# SCH_ESQUEMA_EASY_EDA_2026-10-01.net
KiCad netlist of a schematic drawn in EasyEDA
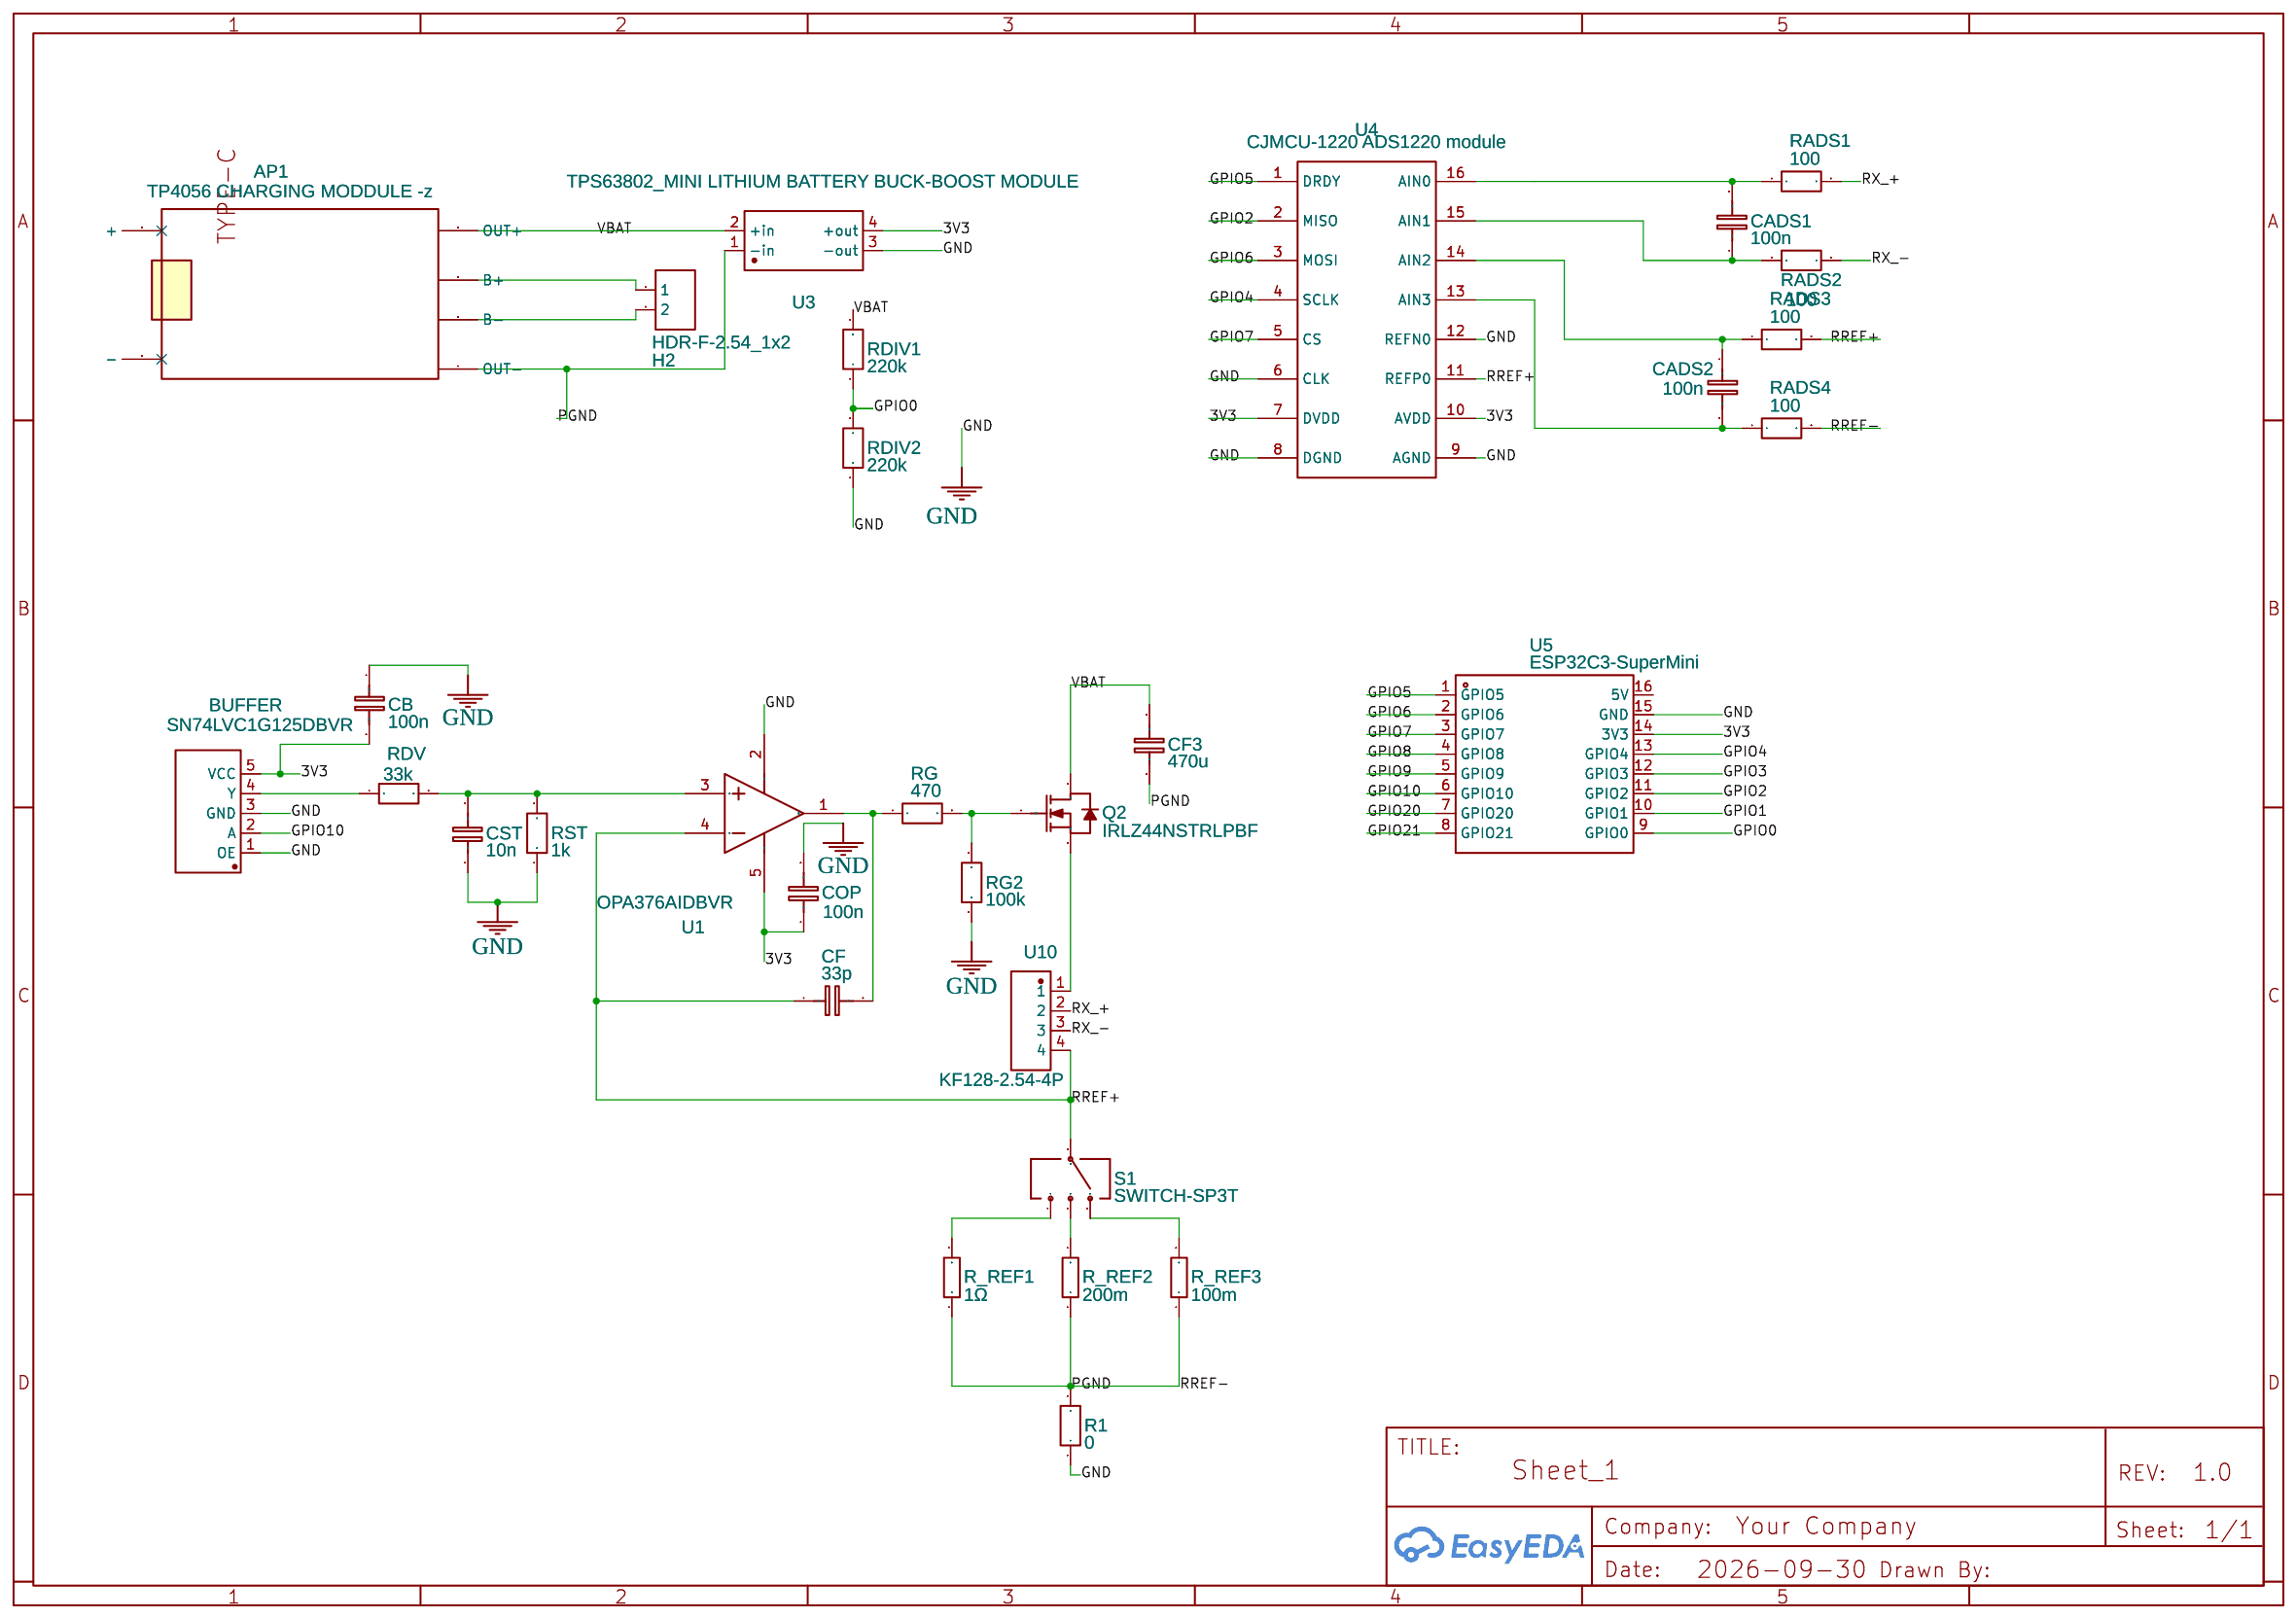
[diagram p0: schematic sheet]

(export (version "E")
  (design (tool "Eeschema 10.0.6"))
  (components
    (comp (ref "AP1")
      (value "TP4056 CHARGING MODDULE -z")
      (fields (field (name "Manufacturer Part") "TP4056"))
      (libsource (lib "") (part "TP4056 CHARGING MODDULE"))
    )
    (comp (ref "BUFFER")
      (value "SN74LVC1G125DBVR")
      (fields (field (name "Manufacturer") "TI(德州仪器)"))
      (libsource (lib "") (part "SN74LVC1G125DBVR"))
    )
    (comp (ref "CADS1") (value "100n") (libsource (lib "") (part "C_0603_EU_3")))
    (comp (ref "CADS2") (value "100n") (libsource (lib "") (part "C_0603_EU_6")))
    (comp (ref "CB") (value "100n") (libsource (lib "") (part "C_0603_EU_2")))
    (comp (ref "CF") (value "33p") (libsource (lib "") (part "C_0603_EU")))
    (comp (ref "CF3") (value "470u") (libsource (lib "") (part "C_0603_EU_1")))
    (comp (ref "COP") (value "100n") (libsource (lib "") (part "C_0603_EU_5")))
    (comp (ref "CST") (value "10n") (libsource (lib "") (part "C_0603_EU_4")))
    (comp (ref "H2") (value "HDR-F-2.54_1x2") (libsource (lib "") (part "HDR-F-2.54_1x2")))
    (comp (ref "Q2")
      (value "IRLZ44NSTRLPBF")
      (fields (field (name "Manufacturer") "Infineon(英飞凌)"))
      (libsource (lib "") (part "IRLZ44NSTRLPBF"))
    )
    (comp (ref "R1") (value "0") (libsource (lib "") (part "R_0603_EU_4")))
    (comp (ref "RADS1") (value "100") (libsource (lib "") (part "R_0603_EU_2")))
    (comp (ref "RADS2") (value "100") (libsource (lib "") (part "R_0603_EU_2")))
    (comp (ref "RADS3") (value "100") (libsource (lib "") (part "R_0603_EU_2")))
    (comp (ref "RADS4") (value "100") (libsource (lib "") (part "R_0603_EU_2")))
    (comp (ref "RDIV1") (value "220k") (libsource (lib "") (part "R_0603_EU_1")))
    (comp (ref "RDIV2") (value "220k") (libsource (lib "") (part "R_0603_EU_1")))
    (comp (ref "RDV") (value "33k") (libsource (lib "") (part "R_0603_EU")))
    (comp (ref "RG") (value "470") (libsource (lib "") (part "R_0603_EU_3")))
    (comp (ref "RG2") (value "100k") (libsource (lib "") (part "R_0603_EU_6")))
    (comp (ref "RST") (value "1k") (libsource (lib "") (part "R_0603_EU_5")))
    (comp (ref "R_REF1")
      (value "1Ω")
      (fields (field (name "Manufacturer Part") "RC1206FR-071RL") (field (name "Manufacturer") "YAGEO(国巨)"))
      (libsource (lib "") (part "RC1206FR-071RL"))
    )
    (comp (ref "R_REF2")
      (value "200m")
      (fields (field (name "Manufacturer Part") "0.16Ω±1%2W-2512"))
      (libsource (lib "") (part "0.16Ω±1%2W-2512"))
    )
    (comp (ref "R_REF3")
      (value "100m")
      (fields (field (name "Manufacturer Part") "0.16Ω±1%2W-2512"))
      (libsource (lib "") (part "0.16Ω±1%2W-2512"))
    )
    (comp (ref "S1") (value "SWITCH-SP3T") (libsource (lib "") (part "SWITCH-SP3T")))
    (comp (ref "U1")
      (value "OPA376AIDBVR")
      (fields (field (name "Manufacturer") "TI(德州仪器)"))
      (libsource (lib "") (part "OPA376AIDBVR"))
    )
    (comp (ref "U3")
      (value "TPS63802_MINI LITHIUM BATTERY BUCK-BOOST MODULE")
      (libsource (lib "") (part "TPS63802_MINI LITHIUM BATTERY BUCK-BOOST MODULE"))
    )
    (comp (ref "U4")
      (value "CJMCU-1220 ADS1220 module")
      (libsource (lib "") (part "CJMCU-1220 ADS1220 module"))
    )
    (comp (ref "U5") (value "ESP32C3-SuperMini") (libsource (lib "") (part "ESP32C3-SuperMini")))
    (comp (ref "U10")
      (value "KF128-2.54-4P")
      (fields (field (name "Manufacturer") "KEFA(科发)"))
      (libsource (lib "") (part "KF128-2.54-4P"))
    )
  )
  (nets
    (net (code "1") (name "/3V3") (class "Default")
      (node (ref "BUFFER") (pin "5") (pinfunction "VCC_5") (pintype "unspecified"))
      (node (ref "CB") (pin "2") (pinfunction "2_2") (pintype "unspecified"))
      (node (ref "COP") (pin "1") (pinfunction "1_1") (pintype "unspecified"))
      (node (ref "U1") (pin "5") (pinfunction "V+_5") (pintype "passive"))
      (node (ref "U3") (pin "4") (pinfunction "+out_4") (pintype "unspecified"))
      (node (ref "U4") (pin "10") (pinfunction "AVDD_10") (pintype "unspecified"))
      (node (ref "U4") (pin "7") (pinfunction "DVDD_7") (pintype "unspecified"))
      (node (ref "U5") (pin "14") (pinfunction "3V3_14") (pintype "unspecified"))
    )
    (net (code "2") (name "/GPIO0") (class "Default")
      (node (ref "RDIV1") (pin "1") (pinfunction "1_1") (pintype "unspecified"))
      (node (ref "RDIV2") (pin "2") (pinfunction "2_2") (pintype "unspecified"))
      (node (ref "U5") (pin "9") (pinfunction "GPIO0_9") (pintype "unspecified"))
    )
    (net (code "3") (name "/GPIO1") (class "Default")
      (node (ref "U5") (pin "10") (pinfunction "GPIO1_10") (pintype "unspecified"))
    )
    (net (code "4") (name "/GPIO2") (class "Default")
      (node (ref "U4") (pin "2") (pinfunction "MISO_2") (pintype "unspecified"))
      (node (ref "U5") (pin "11") (pinfunction "GPIO2_11") (pintype "unspecified"))
    )
    (net (code "5") (name "/GPIO3") (class "Default")
      (node (ref "U5") (pin "12") (pinfunction "GPIO3_12") (pintype "unspecified"))
    )
    (net (code "6") (name "/GPIO4") (class "Default")
      (node (ref "U4") (pin "4") (pinfunction "SCLK_4") (pintype "unspecified"))
      (node (ref "U5") (pin "13") (pinfunction "GPIO4_13") (pintype "unspecified"))
    )
    (net (code "7") (name "/GPIO5") (class "Default")
      (node (ref "U4") (pin "1") (pinfunction "DRDY_1") (pintype "unspecified"))
      (node (ref "U5") (pin "1") (pinfunction "GPIO5_1") (pintype "unspecified"))
    )
    (net (code "8") (name "/GPIO6") (class "Default")
      (node (ref "U4") (pin "3") (pinfunction "MOSI_3") (pintype "unspecified"))
      (node (ref "U5") (pin "2") (pinfunction "GPIO6_2") (pintype "unspecified"))
    )
    (net (code "9") (name "/GPIO7") (class "Default")
      (node (ref "U4") (pin "5") (pinfunction "CS_5") (pintype "unspecified"))
      (node (ref "U5") (pin "3") (pinfunction "GPIO7_3") (pintype "unspecified"))
    )
    (net (code "10") (name "/GPIO8") (class "Default")
      (node (ref "U5") (pin "4") (pinfunction "GPIO8_4") (pintype "unspecified"))
    )
    (net (code "11") (name "/GPIO9") (class "Default")
      (node (ref "U5") (pin "5") (pinfunction "GPIO9_5") (pintype "unspecified"))
    )
    (net (code "12") (name "/GPIO10") (class "Default")
      (node (ref "BUFFER") (pin "2") (pinfunction "A_2") (pintype "unspecified"))
      (node (ref "U5") (pin "6") (pinfunction "GPIO10_6") (pintype "unspecified"))
    )
    (net (code "13") (name "/GPIO20") (class "Default")
      (node (ref "U5") (pin "7") (pinfunction "GPIO20_7") (pintype "unspecified"))
    )
    (net (code "14") (name "/GPIO21") (class "Default")
      (node (ref "U5") (pin "8") (pinfunction "GPIO21_8") (pintype "unspecified"))
    )
    (net (code "15") (name "/PGND") (class "Default")
      (node (ref "AP1") (pin "4") (pinfunction "OUT-_4") (pintype "unspecified"))
      (node (ref "CF3") (pin "1") (pinfunction "1_1") (pintype "unspecified"))
      (node (ref "R1") (pin "2") (pinfunction "2_2") (pintype "unspecified"))
      (node (ref "RADS4") (pin "2") (pinfunction "2_2") (pintype "unspecified"))
      (node (ref "R_REF1") (pin "1") (pinfunction "1_1") (pintype "input"))
      (node (ref "R_REF2") (pin "1") (pinfunction "1_1") (pintype "unspecified"))
      (node (ref "R_REF3") (pin "1") (pinfunction "1_1") (pintype "unspecified"))
      (node (ref "U3") (pin "1") (pinfunction "-in_1") (pintype "unspecified"))
    )
    (net (code "16") (name "/RREF+") (class "Default")
      (node (ref "CF") (pin "1") (pinfunction "1_1") (pintype "unspecified"))
      (node (ref "RADS3") (pin "2") (pinfunction "2_2") (pintype "unspecified"))
      (node (ref "S1") (pin "3") (pinfunction "3_3") (pintype "unspecified"))
      (node (ref "U1") (pin "4") (pinfunction "IN-_4") (pintype "unspecified"))
      (node (ref "U10") (pin "4") (pinfunction "4_4") (pintype "unspecified"))
      (node (ref "U4") (pin "11") (pinfunction "REFP0_11") (pintype "unspecified"))
    )
    (net (code "17") (name "/RX_+") (class "Default")
      (node (ref "RADS1") (pin "2") (pinfunction "2_2") (pintype "unspecified"))
      (node (ref "U10") (pin "2") (pinfunction "2_2") (pintype "unspecified"))
    )
    (net (code "18") (name "/RX_-") (class "Default")
      (node (ref "RADS2") (pin "2") (pinfunction "2_2") (pintype "unspecified"))
      (node (ref "U10") (pin "3") (pinfunction "3_3") (pintype "unspecified"))
    )
    (net (code "19") (name "/VBAT") (class "Default")
      (node (ref "AP1") (pin "3") (pinfunction "OUT+_3") (pintype "unspecified"))
      (node (ref "CF3") (pin "2") (pinfunction "2_2") (pintype "unspecified"))
      (node (ref "Q2") (pin "2") (pinfunction "D_2") (pintype "unspecified"))
      (node (ref "RDIV1") (pin "2") (pinfunction "2_2") (pintype "unspecified"))
      (node (ref "U3") (pin "2") (pinfunction "+in_2") (pintype "unspecified"))
    )
    (net (code "20") (name "GND") (class "Default")
      (node (ref "BUFFER") (pin "1") (pinfunction "OE_1") (pintype "unspecified"))
      (node (ref "BUFFER") (pin "3") (pinfunction "GND_3") (pintype "unspecified"))
      (node (ref "CB") (pin "1") (pinfunction "1_1") (pintype "unspecified"))
      (node (ref "COP") (pin "2") (pinfunction "2_2") (pintype "unspecified"))
      (node (ref "CST") (pin "1") (pinfunction "1_1") (pintype "unspecified"))
      (node (ref "R1") (pin "1") (pinfunction "1_1") (pintype "unspecified"))
      (node (ref "RDIV2") (pin "1") (pinfunction "1_1") (pintype "unspecified"))
      (node (ref "RG2") (pin "1") (pinfunction "1_1") (pintype "unspecified"))
      (node (ref "RST") (pin "1") (pinfunction "1_1") (pintype "unspecified"))
      (node (ref "U1") (pin "2") (pinfunction "V-_2") (pintype "passive"))
      (node (ref "U3") (pin "3") (pinfunction "-out_3") (pintype "unspecified"))
      (node (ref "U4") (pin "12") (pinfunction "REFN0_12") (pintype "unspecified"))
      (node (ref "U4") (pin "6") (pinfunction "CLK_6") (pintype "unspecified"))
      (node (ref "U4") (pin "8") (pinfunction "DGND_8") (pintype "unspecified"))
      (node (ref "U4") (pin "9") (pinfunction "AGND_9") (pintype "unspecified"))
      (node (ref "U5") (pin "15") (pinfunction "GND_15") (pintype "unspecified"))
    )
    (net (code "21") (name "Net-(AP1-B+)") (class "Default")
      (node (ref "AP1") (pin "1") (pinfunction "B+_1") (pintype "unspecified"))
      (node (ref "H2") (pin "1") (pinfunction "1_1") (pintype "input"))
    )
    (net (code "22") (name "Net-(AP1-B-)") (class "Default")
      (node (ref "AP1") (pin "2") (pinfunction "B-_2") (pintype "unspecified"))
      (node (ref "H2") (pin "2") (pinfunction "2_2") (pintype "input"))
    )
    (net (code "23") (name "Net-(BUFFER-Y)") (class "Default")
      (node (ref "BUFFER") (pin "4") (pinfunction "Y_4") (pintype "unspecified"))
      (node (ref "RDV") (pin "1") (pinfunction "1_1") (pintype "unspecified"))
    )
    (net (code "24") (name "Net-(Q2-G)") (class "Default")
      (node (ref "Q2") (pin "1") (pinfunction "G_1") (pintype "unspecified"))
      (node (ref "RG") (pin "2") (pinfunction "2_2") (pintype "unspecified"))
      (node (ref "RG2") (pin "2") (pinfunction "2_2") (pintype "unspecified"))
    )
    (net (code "25") (name "Net-(Q2-S)") (class "Default")
      (node (ref "Q2") (pin "3") (pinfunction "S_3") (pintype "unspecified"))
      (node (ref "U10") (pin "1") (pinfunction "1_1") (pintype "unspecified"))
    )
    (net (code "26") (name "Net-(R_REF1-Pad2)") (class "Default")
      (node (ref "R_REF1") (pin "2") (pinfunction "2_2") (pintype "input"))
      (node (ref "S1") (pin "4") (pinfunction "4_4") (pintype "unspecified"))
    )
    (net (code "27") (name "Net-(R_REF2-Pad2)") (class "Default")
      (node (ref "R_REF2") (pin "2") (pinfunction "2_2") (pintype "unspecified"))
      (node (ref "S1") (pin "2") (pinfunction "2_2") (pintype "unspecified"))
    )
    (net (code "28") (name "Net-(R_REF3-Pad2)") (class "Default")
      (node (ref "R_REF3") (pin "2") (pinfunction "2_2") (pintype "unspecified"))
      (node (ref "S1") (pin "1") (pinfunction "1_1") (pintype "unspecified"))
    )
    (net (code "29") (name "Net-(U1-IN+)") (class "Default")
      (node (ref "CST") (pin "2") (pinfunction "2_2") (pintype "unspecified"))
      (node (ref "RDV") (pin "2") (pinfunction "2_2") (pintype "unspecified"))
      (node (ref "RST") (pin "2") (pinfunction "2_2") (pintype "unspecified"))
      (node (ref "U1") (pin "3") (pinfunction "IN+_3") (pintype "unspecified"))
    )
    (net (code "30") (name "Net-(U1-OUT)") (class "Default")
      (node (ref "CF") (pin "2") (pinfunction "2_2") (pintype "unspecified"))
      (node (ref "RG") (pin "1") (pinfunction "1_1") (pintype "unspecified"))
      (node (ref "U1") (pin "1") (pinfunction "OUT_1") (pintype "output"))
    )
    (net (code "31") (name "Net-(U4-AIN0)") (class "Default")
      (node (ref "CADS1") (pin "2") (pinfunction "2_2") (pintype "unspecified"))
      (node (ref "RADS1") (pin "1") (pinfunction "1_1") (pintype "unspecified"))
      (node (ref "U4") (pin "16") (pinfunction "AIN0_16") (pintype "unspecified"))
    )
    (net (code "32") (name "Net-(U4-AIN1)") (class "Default")
      (node (ref "CADS1") (pin "1") (pinfunction "1_1") (pintype "unspecified"))
      (node (ref "RADS2") (pin "1") (pinfunction "1_1") (pintype "unspecified"))
      (node (ref "U4") (pin "15") (pinfunction "AIN1_15") (pintype "unspecified"))
    )
    (net (code "33") (name "Net-(U4-AIN2)") (class "Default")
      (node (ref "CADS2") (pin "1") (pinfunction "1_1") (pintype "unspecified"))
      (node (ref "RADS3") (pin "1") (pinfunction "1_1") (pintype "unspecified"))
      (node (ref "U4") (pin "14") (pinfunction "AIN2_14") (pintype "unspecified"))
    )
    (net (code "34") (name "Net-(U4-AIN3)") (class "Default")
      (node (ref "CADS2") (pin "2") (pinfunction "2_2") (pintype "unspecified"))
      (node (ref "RADS4") (pin "1") (pinfunction "1_1") (pintype "unspecified"))
      (node (ref "U4") (pin "13") (pinfunction "AIN3_13") (pintype "unspecified"))
    )
    (net (code "35") (name "unconnected-(AP1-+-Pad5)") (class "Default")
      (node (ref "AP1") (pin "5") (pinfunction "+_5") (pintype "unspecified+no_connect"))
    )
    (net (code "36") (name "unconnected-(AP1---Pad6)") (class "Default")
      (node (ref "AP1") (pin "6") (pinfunction "-_6") (pintype "unspecified+no_connect"))
    )
    (net (code "37") (name "unconnected-(U5-5V-Pad16)") (class "Default")
      (node (ref "U5") (pin "16") (pinfunction "5V_16") (pintype "unspecified"))
    )
  )
)
